# design.net
KiCad netlist of a schematic drawn in Altium Designer
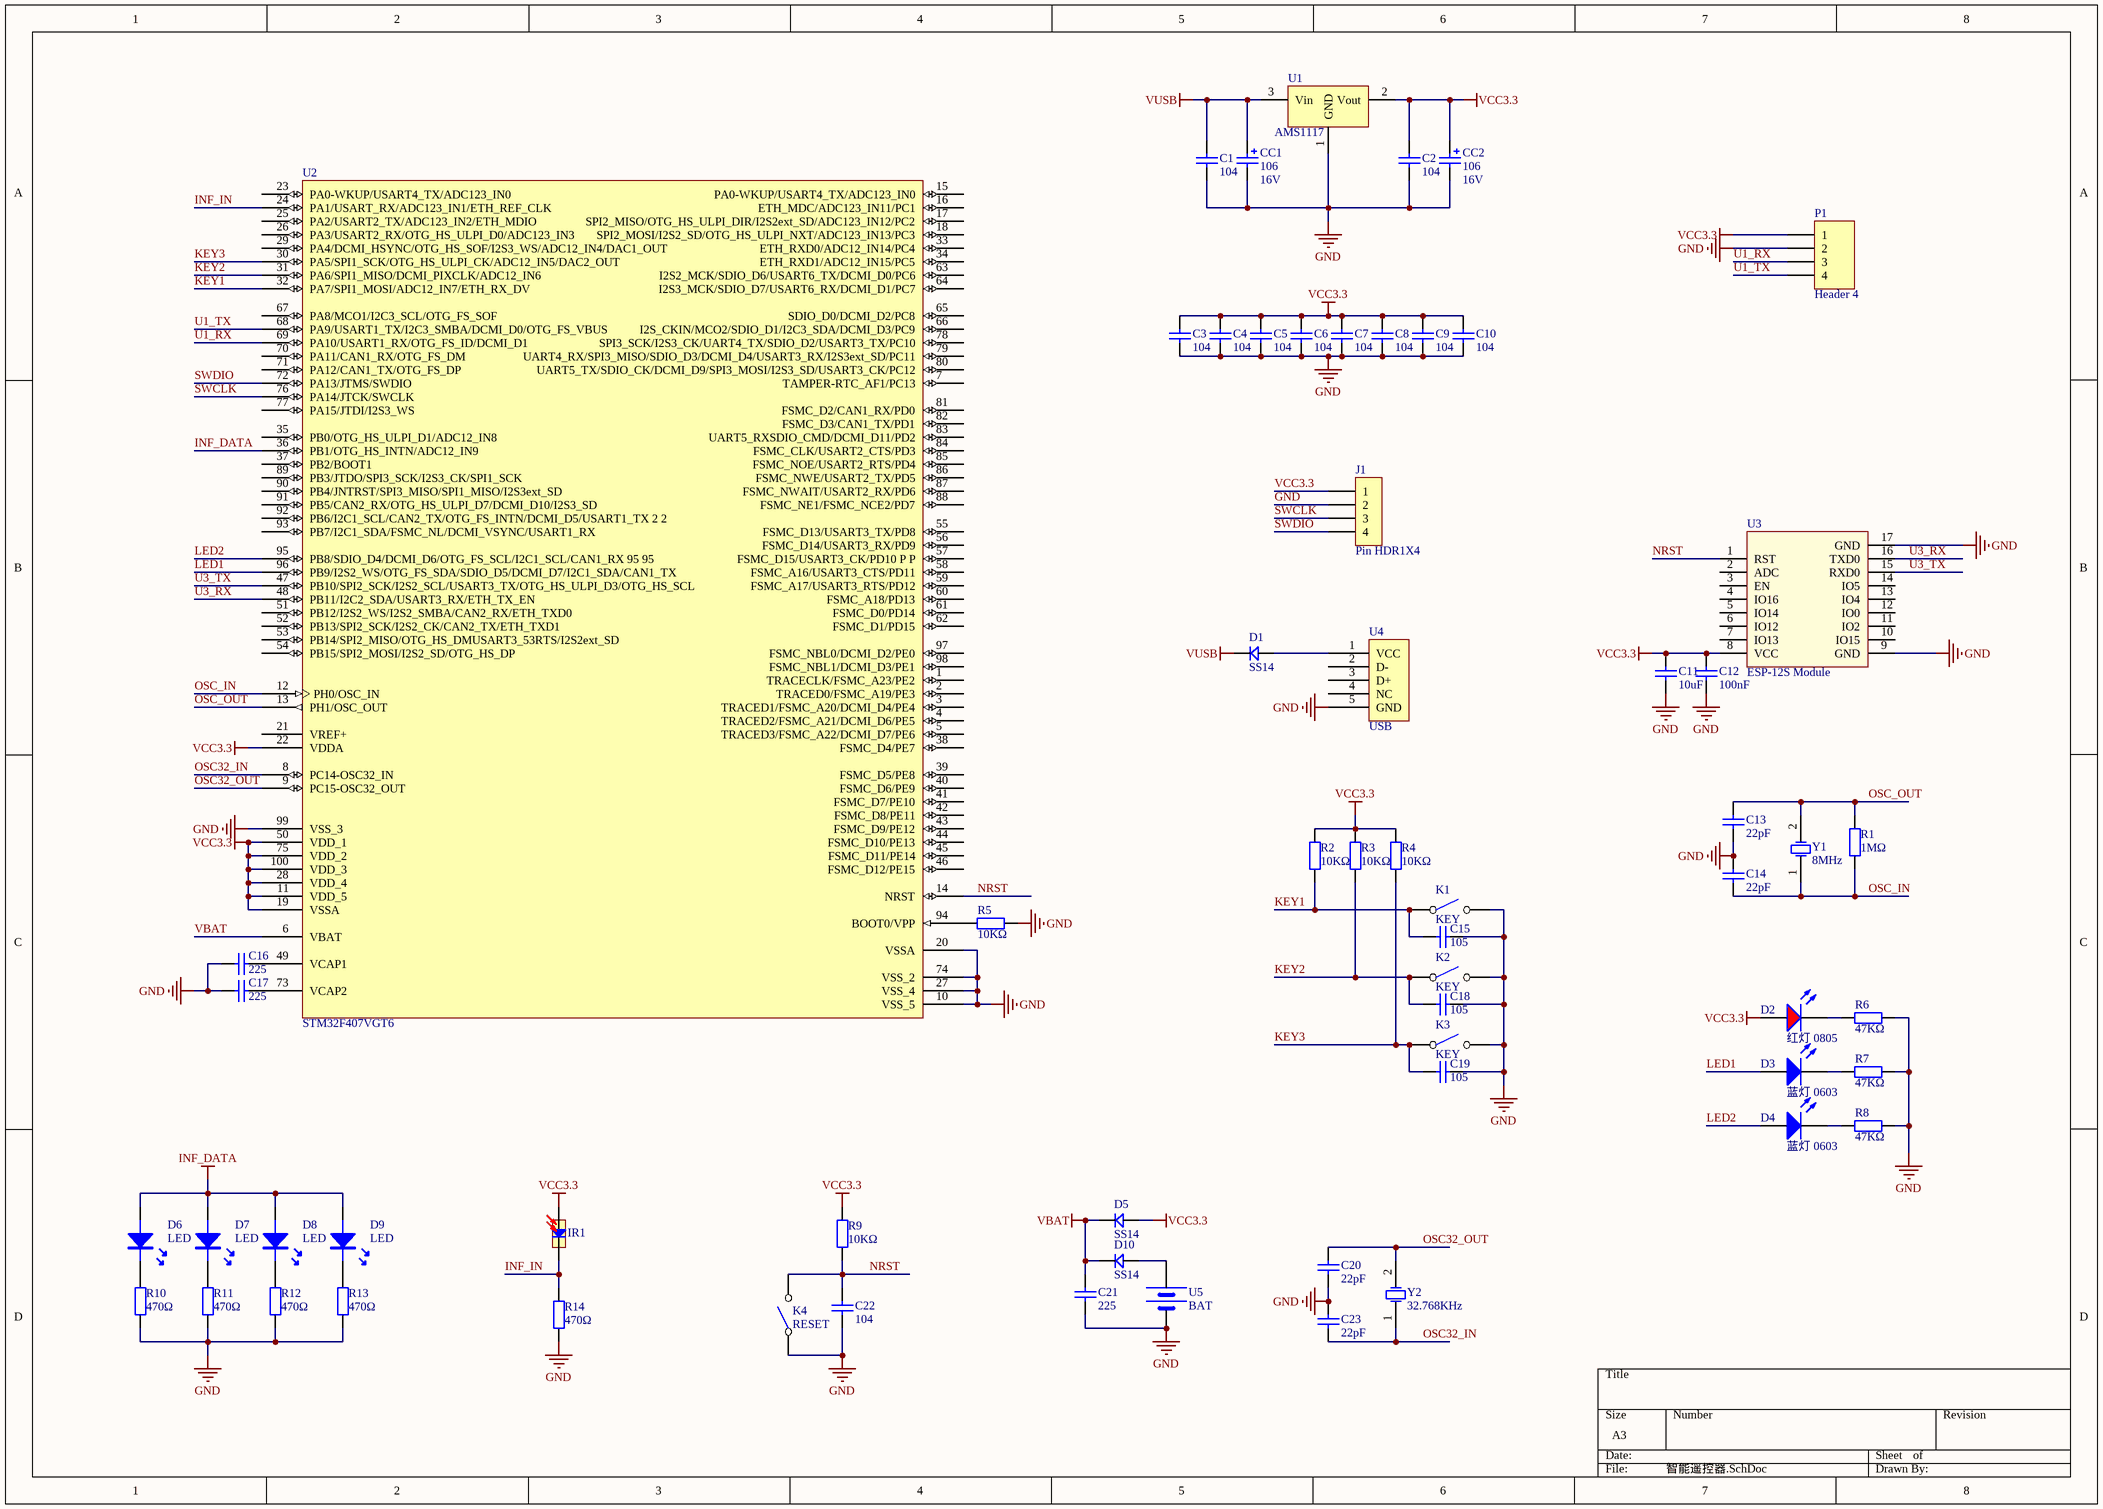
[diagram p0: 智能遥控器.SchDoc]

(export (version "E")
  (design (tool "Eeschema 10.0.6"))
  (components
    (comp (ref "C1")
      (value "104")
      (footprint "LC-0805_C")
      (description "贴片电容")
      (libsource (lib "Miscellaneous Devices LC") (part "0805 6.8nF (682) 10% 50V"))
    )
    (comp (ref "C2")
      (value "104")
      (footprint "LC-0805_C")
      (description "贴片电容")
      (libsource (lib "Miscellaneous Devices LC") (part "0805 6.8nF (682) 10% 50V"))
    )
    (comp (ref "C3")
      (value "104")
      (footprint "LC-0805_C")
      (description "贴片电容")
      (libsource (lib "Miscellaneous Devices LC") (part "0805 6.8nF (682) 10% 50V"))
    )
    (comp (ref "C4")
      (value "104")
      (footprint "LC-0805_C")
      (description "贴片电容")
      (libsource (lib "Miscellaneous Devices LC") (part "0805 6.8nF (682) 10% 50V"))
    )
    (comp (ref "C5")
      (value "104")
      (footprint "LC-0805_C")
      (description "贴片电容")
      (libsource (lib "Miscellaneous Devices LC") (part "0805 6.8nF (682) 10% 50V"))
    )
    (comp (ref "C6")
      (value "104")
      (footprint "LC-0805_C")
      (description "贴片电容")
      (libsource (lib "Miscellaneous Devices LC") (part "0805 6.8nF (682) 10% 50V"))
    )
    (comp (ref "C7")
      (value "104")
      (footprint "LC-0805_C")
      (description "贴片电容")
      (libsource (lib "Miscellaneous Devices LC") (part "0805 6.8nF (682) 10% 50V"))
    )
    (comp (ref "C8")
      (value "104")
      (footprint "LC-0805_C")
      (description "贴片电容")
      (libsource (lib "Miscellaneous Devices LC") (part "0805 6.8nF (682) 10% 50V"))
    )
    (comp (ref "C9")
      (value "104")
      (footprint "LC-0805_C")
      (description "贴片电容")
      (libsource (lib "Miscellaneous Devices LC") (part "0805 6.8nF (682) 10% 50V"))
    )
    (comp (ref "C10")
      (value "104")
      (footprint "LC-0805_C")
      (description "贴片电容")
      (libsource (lib "Miscellaneous Devices LC") (part "0805 6.8nF (682) 10% 50V"))
    )
    (comp (ref "C11")
      (value "10uF")
      (footprint "LC-0805_C")
      (description "贴片电容")
      (libsource (lib "Miscellaneous Devices LC") (part "0805 6.8nF (682) 10% 50V"))
    )
    (comp (ref "C12")
      (value "100nF")
      (footprint "LC-0805_C")
      (description "贴片电容")
      (libsource (lib "Miscellaneous Devices LC") (part "0805 6.8nF (682) 10% 50V"))
    )
    (comp (ref "C13")
      (value "22pF")
      (footprint "LC-0805_C")
      (description "贴片电容")
      (libsource (lib "Miscellaneous Devices LC") (part "0805 6pF (6R0) 0.25pF 50V"))
    )
    (comp (ref "C14")
      (value "22pF")
      (footprint "LC-0805_C")
      (description "贴片电容")
      (libsource (lib "Miscellaneous Devices LC") (part "0805 6pF (6R0) 0.25pF 50V"))
    )
    (comp (ref "C15")
      (value "105")
      (footprint "LC-0805_C")
      (description "贴片电容")
      (libsource (lib "Miscellaneous Devices LC") (part "0805 6.8nF (682) 10% 50V"))
    )
    (comp (ref "C16")
      (value "225")
      (footprint "LC-0805_C")
      (description "贴片电容")
      (libsource (lib "Miscellaneous Devices LC") (part "0805 6.8nF (682) 10% 50V"))
    )
    (comp (ref "C17")
      (value "225")
      (footprint "LC-0805_C")
      (description "贴片电容")
      (libsource (lib "Miscellaneous Devices LC") (part "0805 6.8nF (682) 10% 50V"))
    )
    (comp (ref "C18")
      (value "105")
      (footprint "LC-0805_C")
      (description "贴片电容")
      (libsource (lib "Miscellaneous Devices LC") (part "0805 6.8nF (682) 10% 50V"))
    )
    (comp (ref "C19")
      (value "105")
      (footprint "LC-0805_C")
      (description "贴片电容")
      (libsource (lib "Miscellaneous Devices LC") (part "0805 6.8nF (682) 10% 50V"))
    )
    (comp (ref "C20")
      (value "22pF")
      (footprint "LC-0805_C")
      (description "贴片电容")
      (libsource (lib "Miscellaneous Devices LC") (part "0805 6pF (6R0) 0.25pF 50V"))
    )
    (comp (ref "C21")
      (value "225")
      (footprint "LC-0805_C")
      (description "贴片电容")
      (libsource (lib "Miscellaneous Devices LC") (part "0805 6.8nF (682) 10% 50V"))
    )
    (comp (ref "C22")
      (value "104")
      (footprint "LC-0805_C")
      (description "贴片电容")
      (libsource (lib "Miscellaneous Devices LC") (part "0805 330nF (334) 10% 50V"))
    )
    (comp (ref "C23")
      (value "22pF")
      (footprint "LC-0805_C")
      (description "贴片电容")
      (libsource (lib "Miscellaneous Devices LC") (part "0805 6pF (6R0) 0.25pF 50V"))
    )
    (comp (ref "CC1")
      (value "Cap Tan C")
      (footprint "TAN-C-6032")
      (description "Polarized Capacitor (Radial)")
      (fields
        (field (name "CAPACITANCE") "106")
        (field (name "VOLTAGE") "16V")
        (field (name "PUBLISHER") "Altium Limited")
      )
      (libsource (lib "MyLib") (part "Cap Tan C"))
    )
    (comp (ref "CC2")
      (value "Cap Tan C")
      (footprint "TAN-C-6032")
      (description "Polarized Capacitor (Radial)")
      (fields
        (field (name "CAPACITANCE") "106")
        (field (name "VOLTAGE") "16V")
        (field (name "PUBLISHER") "Altium Limited")
      )
      (libsource (lib "MyLib") (part "Cap Tan C"))
    )
    (comp (ref "D1")
      (value "SS14")
      (footprint "Miscellaneous Devices LC:LC-SOD-123")
      (libsource (lib "Explorer STM32F407封装库") (part "D"))
    )
    (comp (ref "D2")
      (value "红灯 0805")
      (footprint "LC-0805_LED_S1")
      (description "发光二极管")
      (libsource (lib "Miscellaneous Devices LC") (part "0805 红灯"))
    )
    (comp (ref "D3")
      (value "蓝灯 0603")
      (footprint "Miscellaneous Devices LC:LC-0805_LED_S1")
      (description "发光二极管")
      (libsource (lib "Miscellaneous Devices LC") (part "0603 蓝灯"))
    )
    (comp (ref "D4")
      (value "蓝灯 0603")
      (footprint "Miscellaneous Devices LC:LC-0805_LED_S1")
      (description "发光二极管")
      (libsource (lib "Miscellaneous Devices LC") (part "0603 蓝灯"))
    )
    (comp (ref "D5")
      (value "SS14")
      (footprint "Miscellaneous Devices LC:LC-SOD-123")
      (libsource (lib "Explorer STM32F407封装库") (part "D"))
    )
    (comp (ref "D6") (value "LED") (footprint "LED5-RED") (libsource (lib "LED") (part "LED")))
    (comp (ref "D7") (value "LED") (footprint "LED5-RED") (libsource (lib "LED") (part "LED")))
    (comp (ref "D8") (value "LED") (footprint "LED5-RED") (libsource (lib "LED") (part "LED")))
    (comp (ref "D9") (value "LED") (footprint "LED5-RED") (libsource (lib "LED") (part "LED")))
    (comp (ref "D10")
      (value "SS14")
      (footprint "Miscellaneous Devices LC:LC-SOD-123")
      (libsource (lib "Explorer STM32F407封装库") (part "D"))
    )
    (comp (ref "IR1")
      (value "IR")
      (footprint "MyLib:LED-R5-H9-SINGLE-B")
      (description "RED Remote Receiver")
      (libsource (lib "MyLib") (part "IR"))
    )
    (comp (ref "J1")
      (value "Pin HDR1X4")
      (footprint "Pin HDR1X4/2.54mm-S")
      (libsource (lib "排针") (part "Pin HDR1X4"))
    )
    (comp (ref "K1")
      (value "KEY")
      (footprint "MyLib:KEY_2")
      (description "微动开关")
      (libsource (lib "MyLib") (part "KEY"))
    )
    (comp (ref "K2")
      (value "KEY")
      (footprint "MyLib:KEY_2")
      (description "微动开关")
      (libsource (lib "MyLib") (part "KEY"))
    )
    (comp (ref "K3")
      (value "KEY")
      (footprint "MyLib:KEY_2")
      (description "微动开关")
      (libsource (lib "MyLib") (part "KEY"))
    )
    (comp (ref "K4")
      (value "RESET")
      (footprint "MyLib:KEY_2")
      (description "微动开关")
      (libsource (lib "MyLib") (part "KEY"))
    )
    (comp (ref "P1")
      (value "Header 4")
      (footprint "MyLib:HDR1X4")
      (description "Header, 4-Pin")
      (fields (field (name "PUBLISHER") "Altium Limited"))
      (libsource (lib "MyLib") (part "Header 4"))
    )
    (comp (ref "R1")
      (value "1MΩ")
      (footprint "LC-0805_R")
      (description "贴片电阻")
      (libsource (lib "Miscellaneous Devices LC") (part "0805 390KΩ (3903) 1%"))
    )
    (comp (ref "R2")
      (value "10KΩ")
      (footprint "LC-0805_R")
      (description "贴片电阻")
      (libsource (lib "Miscellaneous Devices LC") (part "0805 11KΩ (1102) 1%"))
    )
    (comp (ref "R3")
      (value "10KΩ")
      (footprint "LC-0805_R")
      (description "贴片电阻")
      (libsource (lib "Miscellaneous Devices LC") (part "0805 11KΩ (1102) 1%"))
    )
    (comp (ref "R4")
      (value "10KΩ")
      (footprint "LC-0805_R")
      (description "贴片电阻")
      (libsource (lib "Miscellaneous Devices LC") (part "0805 11KΩ (1102) 1%"))
    )
    (comp (ref "R5")
      (value "10KΩ")
      (footprint "LC-0805_R")
      (description "贴片电阻")
      (libsource (lib "Miscellaneous Devices LC") (part "0805 1.8KΩ (1801) 1%"))
    )
    (comp (ref "R6")
      (value "47KΩ")
      (footprint "LC-0805_R")
      (description "贴片电阻")
      (libsource (lib "") (part "0805 11KΩ (1102) 1%_1"))
    )
    (comp (ref "R7")
      (value "47KΩ")
      (footprint "LC-0805_R")
      (description "贴片电阻")
      (libsource (lib "") (part "0805 11KΩ (1102) 1%_1"))
    )
    (comp (ref "R8")
      (value "47KΩ")
      (footprint "LC-0805_R")
      (description "贴片电阻")
      (libsource (lib "") (part "0805 11KΩ (1102) 1%_1"))
    )
    (comp (ref "R9")
      (value "10KΩ")
      (footprint "LC-0805_R")
      (description "贴片电阻")
      (libsource (lib "Miscellaneous Devices LC") (part "0805 390KΩ (3903) 1%"))
    )
    (comp (ref "R10")
      (value "470Ω")
      (footprint "LC-0805_R")
      (description "贴片电阻")
      (libsource (lib "Miscellaneous Devices LC") (part "0805 11KΩ (1102) 1%"))
    )
    (comp (ref "R11")
      (value "470Ω")
      (footprint "LC-0805_R")
      (description "贴片电阻")
      (libsource (lib "Miscellaneous Devices LC") (part "0805 11KΩ (1102) 1%"))
    )
    (comp (ref "R12")
      (value "470Ω")
      (footprint "LC-0805_R")
      (description "贴片电阻")
      (libsource (lib "Miscellaneous Devices LC") (part "0805 11KΩ (1102) 1%"))
    )
    (comp (ref "R13")
      (value "470Ω")
      (footprint "LC-0805_R")
      (description "贴片电阻")
      (libsource (lib "Miscellaneous Devices LC") (part "0805 11KΩ (1102) 1%"))
    )
    (comp (ref "R14")
      (value "470Ω")
      (footprint "LC-0805_R")
      (description "贴片电阻")
      (libsource (lib "Miscellaneous Devices LC") (part "0805 11KΩ (1102) 1%"))
    )
    (comp (ref "U1")
      (value "AMS1117")
      (footprint "MyLib:SOT-223")
      (description "3.3V电压转换器AMS1117")
      (libsource (lib "My Footprint") (part "AMS1117"))
    )
    (comp (ref "U2")
      (value "STM32F407VGT6")
      (footprint "STM32系列:LQFP100 14x14")
      (libsource (lib "STM32F407系列") (part "STM32F407VGT6"))
    )
    (comp (ref "U3")
      (value "ESP-12S Module")
      (footprint "ESP-12S Module")
      (libsource (lib "MyLib") (part "ESP-12S Module"))
    )
    (comp (ref "U4") (value "USB") (footprint "MyLib:USB_B") (libsource (lib "MyLib") (part "USB")))
    (comp (ref "U5")
      (value "BAT")
      (footprint "MyLib:CR1220_A")
      (description "纽扣电池座CR1220")
      (libsource (lib "MyLib") (part "BAT"))
    )
    (comp (ref "Y1")
      (value "8MHz")
      (footprint "MyLib:XTAL-SMD")
      (description "晶体振荡器")
      (fields (field (name "PUBLISHER") "Altium Limited"))
      (libsource (lib "MyLib") (part "XTAL"))
    )
    (comp (ref "Y2")
      (value "32.768KHz")
      (footprint "晶振:OSC-3x8-WI-B")
      (description "晶体振荡器")
      (fields (field (name "PUBLISHER") "Altium Limited"))
      (libsource (lib "MyLib") (part "XTAL"))
    )
  )
  (nets
    (net (code "1") (name "/INF_IN") (class "Default")
      (node (ref "IR1") (pin "2") (pinfunction "GND_2") (pintype "passive"))
      (node (ref "R14") (pin "2") (pinfunction "2_2") (pintype "passive"))
      (node (ref "U2") (pin "24") (pinfunction "PA1/USART_RX/ADC123_IN1/ETH_REF_CLK_24") (pintype "bidirectional"))
    )
    (net (code "2") (name "/KEY1") (class "Default")
      (node (ref "C15") (pin "1") (pinfunction "1_1") (pintype "passive"))
      (node (ref "K1") (pin "1") (pinfunction "1_1") (pintype "passive"))
      (node (ref "R2") (pin "1") (pinfunction "1_1") (pintype "passive"))
      (node (ref "U2") (pin "32") (pinfunction "PA7/SPI1_MOSI/ADC12_IN7/ETH_RX_DV_32") (pintype "bidirectional"))
    )
    (net (code "3") (name "/KEY2") (class "Default")
      (node (ref "C18") (pin "1") (pinfunction "1_1") (pintype "passive"))
      (node (ref "K2") (pin "1") (pinfunction "1_1") (pintype "passive"))
      (node (ref "R3") (pin "1") (pinfunction "1_1") (pintype "passive"))
      (node (ref "U2") (pin "31") (pinfunction "PA6/SPI1_MISO/DCMI_PIXCLK/ADC12_IN6_31") (pintype "bidirectional"))
    )
    (net (code "4") (name "/KEY3") (class "Default")
      (node (ref "C19") (pin "1") (pinfunction "1_1") (pintype "passive"))
      (node (ref "K3") (pin "1") (pinfunction "1_1") (pintype "passive"))
      (node (ref "R4") (pin "1") (pinfunction "1_1") (pintype "passive"))
      (node (ref "U2") (pin "30") (pinfunction "PA5/SPI1_SCK/OTG_HS_ULPI_CK/ADC12_IN5/DAC2_OUT_30") (pintype "bidirectional"))
    )
    (net (code "5") (name "/LED1") (class "Default")
      (node (ref "D3") (pin "A") (pinfunction "A_A") (pintype "passive"))
      (node (ref "U2") (pin "96") (pinfunction "PB9/I2S2_WS/OTG_FS_SDA/SDIO_D5/DCMI_D7/I2C1_SDA/CAN1_TX_96") (pintype "bidirectional"))
    )
    (net (code "6") (name "/LED2") (class "Default")
      (node (ref "D4") (pin "A") (pinfunction "A_A") (pintype "passive"))
      (node (ref "U2") (pin "95") (pinfunction "PB8/SDIO_D4/DCMI_D6/OTG_FS_SCL/I2C1_SCL/CAN1_RX_95_95_95") (pintype "bidirectional"))
    )
    (net (code "7") (name "/NRST") (class "Default")
      (node (ref "C22") (pin "2") (pinfunction "2_2") (pintype "passive"))
      (node (ref "K4") (pin "2") (pinfunction "2_2") (pintype "passive"))
      (node (ref "R9") (pin "1") (pinfunction "1_1") (pintype "passive"))
      (node (ref "U2") (pin "14") (pinfunction "NRST_14") (pintype "bidirectional"))
      (node (ref "U3") (pin "1") (pinfunction "RST_1") (pintype "passive"))
    )
    (net (code "8") (name "/OSC32_IN") (class "Default")
      (node (ref "C23") (pin "1") (pinfunction "1_1") (pintype "passive"))
      (node (ref "U2") (pin "8") (pinfunction "PC14-OSC32_IN_8") (pintype "bidirectional"))
      (node (ref "Y2") (pin "1") (pinfunction "OSC1_1") (pintype "passive"))
    )
    (net (code "9") (name "/OSC32_OUT") (class "Default")
      (node (ref "C20") (pin "2") (pinfunction "2_2") (pintype "passive"))
      (node (ref "U2") (pin "9") (pinfunction "PC15-OSC32_OUT_9") (pintype "bidirectional"))
      (node (ref "Y2") (pin "2") (pinfunction "OSC2_2") (pintype "passive"))
    )
    (net (code "10") (name "/OSC_IN") (class "Default")
      (node (ref "C14") (pin "1") (pinfunction "1_1") (pintype "passive"))
      (node (ref "R1") (pin "1") (pinfunction "1_1") (pintype "passive"))
      (node (ref "U2") (pin "12") (pinfunction "PH0/OSC_IN_12") (pintype "input"))
      (node (ref "Y1") (pin "1") (pinfunction "OSC1_1") (pintype "passive"))
    )
    (net (code "11") (name "/OSC_OUT") (class "Default")
      (node (ref "C13") (pin "2") (pinfunction "2_2") (pintype "passive"))
      (node (ref "R1") (pin "2") (pinfunction "2_2") (pintype "passive"))
      (node (ref "U2") (pin "13") (pinfunction "PH1/OSC_OUT_13") (pintype "output"))
      (node (ref "Y1") (pin "2") (pinfunction "OSC2_2") (pintype "passive"))
    )
    (net (code "12") (name "/SWCLK") (class "Default")
      (node (ref "J1") (pin "3") (pinfunction "3_3") (pintype "passive"))
      (node (ref "U2") (pin "76") (pinfunction "PA14/JTCK/SWCLK_76") (pintype "bidirectional"))
    )
    (net (code "13") (name "/SWDIO") (class "Default")
      (node (ref "J1") (pin "4") (pinfunction "4_4") (pintype "passive"))
      (node (ref "U2") (pin "72") (pinfunction "PA13/JTMS/SWDIO_72") (pintype "bidirectional"))
    )
    (net (code "14") (name "/U1_RX") (class "Default")
      (node (ref "P1") (pin "3") (pinfunction "3_3") (pintype "passive"))
      (node (ref "U2") (pin "69") (pinfunction "PA10/USART1_RX/OTG_FS_ID/DCMI_D1_69") (pintype "bidirectional"))
    )
    (net (code "15") (name "/U1_TX") (class "Default")
      (node (ref "P1") (pin "4") (pinfunction "4_4") (pintype "passive"))
      (node (ref "U2") (pin "68") (pinfunction "PA9/USART1_TX/I2C3_SMBA/DCMI_D0/OTG_FS_VBUS_68") (pintype "bidirectional"))
    )
    (net (code "16") (name "/U3_RX") (class "Default")
      (node (ref "U2") (pin "48") (pinfunction "PB11/I2C2_SDA/USART3_RX/ETH_TX_EN_48") (pintype "bidirectional"))
      (node (ref "U3") (pin "16") (pinfunction "TXD0_16") (pintype "passive"))
    )
    (net (code "17") (name "/U3_TX") (class "Default")
      (node (ref "U2") (pin "47") (pinfunction "PB10/SPI2_SCK/I2S2_SCL/USART3_TX/OTG_HS_ULPI_D3/OTG_HS_SCL_47") (pintype "bidirectional"))
      (node (ref "U3") (pin "15") (pinfunction "RXD0_15") (pintype "passive"))
    )
    (net (code "18") (name "GND") (class "Default")
      (node (ref "C1") (pin "1") (pinfunction "1_1") (pintype "passive"))
      (node (ref "C10") (pin "1") (pinfunction "1_1") (pintype "passive"))
      (node (ref "C11") (pin "1") (pinfunction "1_1") (pintype "passive"))
      (node (ref "C12") (pin "1") (pinfunction "1_1") (pintype "passive"))
      (node (ref "C13") (pin "1") (pinfunction "1_1") (pintype "passive"))
      (node (ref "C14") (pin "2") (pinfunction "2_2") (pintype "passive"))
      (node (ref "C15") (pin "2") (pinfunction "2_2") (pintype "passive"))
      (node (ref "C16") (pin "1") (pinfunction "1_1") (pintype "passive"))
      (node (ref "C17") (pin "1") (pinfunction "1_1") (pintype "passive"))
      (node (ref "C18") (pin "2") (pinfunction "2_2") (pintype "passive"))
      (node (ref "C19") (pin "2") (pinfunction "2_2") (pintype "passive"))
      (node (ref "C2") (pin "1") (pinfunction "1_1") (pintype "passive"))
      (node (ref "C20") (pin "1") (pinfunction "1_1") (pintype "passive"))
      (node (ref "C21") (pin "1") (pinfunction "1_1") (pintype "passive"))
      (node (ref "C22") (pin "1") (pinfunction "1_1") (pintype "passive"))
      (node (ref "C23") (pin "2") (pinfunction "2_2") (pintype "passive"))
      (node (ref "C3") (pin "1") (pinfunction "1_1") (pintype "passive"))
      (node (ref "C4") (pin "1") (pinfunction "1_1") (pintype "passive"))
      (node (ref "C5") (pin "1") (pinfunction "1_1") (pintype "passive"))
      (node (ref "C6") (pin "1") (pinfunction "1_1") (pintype "passive"))
      (node (ref "C7") (pin "1") (pinfunction "1_1") (pintype "passive"))
      (node (ref "C8") (pin "1") (pinfunction "1_1") (pintype "passive"))
      (node (ref "C9") (pin "1") (pinfunction "1_1") (pintype "passive"))
      (node (ref "CC1") (pin "1") (pinfunction "2_1") (pintype "passive"))
      (node (ref "CC2") (pin "1") (pinfunction "2_1") (pintype "passive"))
      (node (ref "J1") (pin "2") (pinfunction "2_2") (pintype "passive"))
      (node (ref "K1") (pin "2") (pinfunction "2_2") (pintype "passive"))
      (node (ref "K2") (pin "2") (pinfunction "2_2") (pintype "passive"))
      (node (ref "K3") (pin "2") (pinfunction "2_2") (pintype "passive"))
      (node (ref "K4") (pin "1") (pinfunction "1_1") (pintype "passive"))
      (node (ref "P1") (pin "2") (pinfunction "2_2") (pintype "passive"))
      (node (ref "R10") (pin "1") (pinfunction "1_1") (pintype "passive"))
      (node (ref "R11") (pin "1") (pinfunction "1_1") (pintype "passive"))
      (node (ref "R12") (pin "1") (pinfunction "1_1") (pintype "passive"))
      (node (ref "R13") (pin "1") (pinfunction "1_1") (pintype "passive"))
      (node (ref "R14") (pin "1") (pinfunction "1_1") (pintype "passive"))
      (node (ref "R5") (pin "2") (pinfunction "2_2") (pintype "passive"))
      (node (ref "R6") (pin "2") (pinfunction "2_2") (pintype "passive"))
      (node (ref "R7") (pin "2") (pinfunction "2_2") (pintype "passive"))
      (node (ref "R8") (pin "2") (pinfunction "2_2") (pintype "passive"))
      (node (ref "U1") (pin "1") (pinfunction "GND_1") (pintype "passive"))
      (node (ref "U2") (pin "10") (pinfunction "VSS_5_10") (pintype "power_in"))
      (node (ref "U2") (pin "20") (pinfunction "VSSA_20") (pintype "power_in"))
      (node (ref "U2") (pin "27") (pinfunction "VSS_4_27") (pintype "power_in"))
      (node (ref "U2") (pin "74") (pinfunction "VSS_2_74") (pintype "power_in"))
      (node (ref "U2") (pin "99") (pinfunction "VSS_3_99") (pintype "power_in"))
      (node (ref "U3") (pin "17") (pinfunction "GND_17") (pintype "passive"))
      (node (ref "U3") (pin "9") (pinfunction "GND_9") (pintype "passive"))
      (node (ref "U4") (pin "5") (pinfunction "GND_5") (pintype "passive"))
      (node (ref "U5") (pin "2") (pinfunction "GND_2") (pintype "passive"))
    )
    (net (code "19") (name "INF_DATA") (class "Default")
      (node (ref "D6") (pin "A") (pinfunction "A_A") (pintype "passive"))
      (node (ref "D7") (pin "A") (pinfunction "A_A") (pintype "passive"))
      (node (ref "D8") (pin "A") (pinfunction "A_A") (pintype "passive"))
      (node (ref "D9") (pin "A") (pinfunction "A_A") (pintype "passive"))
      (node (ref "U2") (pin "36") (pinfunction "PB1/OTG_HS_INTN/ADC12_IN9_36") (pintype "bidirectional"))
    )
    (net (code "20") (name "Net-(D2-PadK)") (class "Default")
      (node (ref "D2") (pin "K") (pinfunction "K_K") (pintype "passive"))
      (node (ref "R6") (pin "1") (pinfunction "1_1") (pintype "passive"))
    )
    (net (code "21") (name "Net-(D3-PadK)") (class "Default")
      (node (ref "D3") (pin "K") (pinfunction "K_K") (pintype "passive"))
      (node (ref "R7") (pin "1") (pinfunction "1_1") (pintype "passive"))
    )
    (net (code "22") (name "Net-(D4-PadK)") (class "Default")
      (node (ref "D4") (pin "K") (pinfunction "K_K") (pintype "passive"))
      (node (ref "R8") (pin "1") (pinfunction "1_1") (pintype "passive"))
    )
    (net (code "23") (name "Net-(D6-PadK)") (class "Default")
      (node (ref "D6") (pin "K") (pinfunction "K_K") (pintype "passive"))
      (node (ref "R10") (pin "2") (pinfunction "2_2") (pintype "passive"))
    )
    (net (code "24") (name "Net-(D7-PadK)") (class "Default")
      (node (ref "D7") (pin "K") (pinfunction "K_K") (pintype "passive"))
      (node (ref "R11") (pin "2") (pinfunction "2_2") (pintype "passive"))
    )
    (net (code "25") (name "Net-(D8-PadK)") (class "Default")
      (node (ref "D8") (pin "K") (pinfunction "K_K") (pintype "passive"))
      (node (ref "R12") (pin "2") (pinfunction "2_2") (pintype "passive"))
    )
    (net (code "26") (name "Net-(D9-PadK)") (class "Default")
      (node (ref "D9") (pin "K") (pinfunction "K_K") (pintype "passive"))
      (node (ref "R13") (pin "2") (pinfunction "2_2") (pintype "passive"))
    )
    (net (code "27") (name "Net-(U2-BOOT0{slash}VPP)") (class "Default")
      (node (ref "R5") (pin "1") (pinfunction "1_1") (pintype "passive"))
      (node (ref "U2") (pin "94") (pinfunction "BOOT0/VPP_94") (pintype "input"))
    )
    (net (code "28") (name "Net-(U2-VCAP1)") (class "Default")
      (node (ref "C16") (pin "2") (pinfunction "2_2") (pintype "passive"))
      (node (ref "U2") (pin "49") (pinfunction "VCAP1_49") (pintype "power_in"))
    )
    (net (code "29") (name "Net-(U2-VCAP2)") (class "Default")
      (node (ref "C17") (pin "2") (pinfunction "2_2") (pintype "passive"))
      (node (ref "U2") (pin "73") (pinfunction "VCAP2_73") (pintype "passive"))
    )
    (net (code "30") (name "Net-(U4-VCC)") (class "Default")
      (node (ref "D1") (pin "1") (pintype "passive"))
      (node (ref "U4") (pin "1") (pinfunction "VCC_1") (pintype "passive"))
    )
    (net (code "31") (name "Net-(U5-VCC)") (class "Default")
      (node (ref "D10") (pin "1") (pintype "passive"))
      (node (ref "U5") (pin "1") (pinfunction "VCC_1") (pintype "passive"))
    )
    (net (code "32") (name "VBAT") (class "Default")
      (node (ref "C21") (pin "2") (pinfunction "2_2") (pintype "passive"))
      (node (ref "D10") (pin "2") (pintype "passive"))
      (node (ref "D5") (pin "2") (pintype "passive"))
      (node (ref "U2") (pin "6") (pinfunction "VBAT_6") (pintype "power_in"))
    )
    (net (code "33") (name "VCC3.3") (class "Default")
      (node (ref "C10") (pin "2") (pinfunction "2_2") (pintype "passive"))
      (node (ref "C11") (pin "2") (pinfunction "2_2") (pintype "passive"))
      (node (ref "C12") (pin "2") (pinfunction "2_2") (pintype "passive"))
      (node (ref "C2") (pin "2") (pinfunction "2_2") (pintype "passive"))
      (node (ref "C3") (pin "2") (pinfunction "2_2") (pintype "passive"))
      (node (ref "C4") (pin "2") (pinfunction "2_2") (pintype "passive"))
      (node (ref "C5") (pin "2") (pinfunction "2_2") (pintype "passive"))
      (node (ref "C6") (pin "2") (pinfunction "2_2") (pintype "passive"))
      (node (ref "C7") (pin "2") (pinfunction "2_2") (pintype "passive"))
      (node (ref "C8") (pin "2") (pinfunction "2_2") (pintype "passive"))
      (node (ref "C9") (pin "2") (pinfunction "2_2") (pintype "passive"))
      (node (ref "CC2") (pin "2") (pinfunction "1_2") (pintype "passive"))
      (node (ref "D2") (pin "A") (pinfunction "A_A") (pintype "passive"))
      (node (ref "D5") (pin "1") (pintype "passive"))
      (node (ref "IR1") (pin "1") (pinfunction "VCC_1") (pintype "passive"))
      (node (ref "J1") (pin "1") (pinfunction "1_1") (pintype "passive"))
      (node (ref "P1") (pin "1") (pinfunction "1_1") (pintype "passive"))
      (node (ref "R2") (pin "2") (pinfunction "2_2") (pintype "passive"))
      (node (ref "R3") (pin "2") (pinfunction "2_2") (pintype "passive"))
      (node (ref "R4") (pin "2") (pinfunction "2_2") (pintype "passive"))
      (node (ref "R9") (pin "2") (pinfunction "2_2") (pintype "passive"))
      (node (ref "U1") (pin "2") (pinfunction "Vout_2") (pintype "passive"))
      (node (ref "U2") (pin "100") (pinfunction "VDD_3_100") (pintype "power_in"))
      (node (ref "U2") (pin "11") (pinfunction "VDD_5_11") (pintype "power_in"))
      (node (ref "U2") (pin "19") (pinfunction "VSSA_19") (pintype "power_in"))
      (node (ref "U2") (pin "22") (pinfunction "VDDA_22") (pintype "power_in"))
      (node (ref "U2") (pin "28") (pinfunction "VDD_4_28") (pintype "power_in"))
      (node (ref "U2") (pin "50") (pinfunction "VDD_1_50") (pintype "power_in"))
      (node (ref "U2") (pin "75") (pinfunction "VDD_2_75") (pintype "power_in"))
      (node (ref "U3") (pin "8") (pinfunction "VCC_8") (pintype "passive"))
    )
    (net (code "34") (name "VUSB") (class "Default")
      (node (ref "C1") (pin "2") (pinfunction "2_2") (pintype "passive"))
      (node (ref "CC1") (pin "2") (pinfunction "1_2") (pintype "passive"))
      (node (ref "D1") (pin "2") (pintype "passive"))
      (node (ref "U1") (pin "3") (pinfunction "Vin_3") (pintype "passive"))
    )
    (net (code "35") (name "unconnected-(U2-ETH_MDC{slash}ADC123_IN11{slash}PC1-Pad16)") (class "Default")
      (node (ref "U2") (pin "16") (pinfunction "ETH_MDC/ADC123_IN11/PC1_16") (pintype "bidirectional"))
    )
    (net (code "36") (name "unconnected-(U2-ETH_RXD0{slash}ADC12_IN14{slash}PC4-Pad33)") (class "Default")
      (node (ref "U2") (pin "33") (pinfunction "ETH_RXD0/ADC12_IN14/PC4_33") (pintype "bidirectional"))
    )
    (net (code "37") (name "unconnected-(U2-ETH_RXD1{slash}ADC12_IN15{slash}PC5-Pad34)") (class "Default")
      (node (ref "U2") (pin "34") (pinfunction "ETH_RXD1/ADC12_IN15/PC5_34") (pintype "bidirectional"))
    )
    (net (code "38") (name "unconnected-(U2-FSMC_A16{slash}USART3_CTS{slash}PD11-Pad58)") (class "Default")
      (node (ref "U2") (pin "58") (pinfunction "FSMC_A16/USART3_CTS/PD11_58") (pintype "bidirectional"))
    )
    (net (code "39") (name "unconnected-(U2-FSMC_A17{slash}USART3_RTS{slash}PD12-Pad59)") (class "Default")
      (node (ref "U2") (pin "59") (pinfunction "FSMC_A17/USART3_RTS/PD12_59") (pintype "bidirectional"))
    )
    (net (code "40") (name "unconnected-(U2-FSMC_A18{slash}PD13-Pad60)") (class "Default")
      (node (ref "U2") (pin "60") (pinfunction "FSMC_A18/PD13_60") (pintype "bidirectional"))
    )
    (net (code "41") (name "unconnected-(U2-FSMC_CLK{slash}USART2_CTS{slash}PD3-Pad84)") (class "Default")
      (node (ref "U2") (pin "84") (pinfunction "FSMC_CLK/USART2_CTS/PD3_84") (pintype "bidirectional"))
    )
    (net (code "42") (name "unconnected-(U2-FSMC_D0{slash}PD14-Pad61)") (class "Default")
      (node (ref "U2") (pin "61") (pinfunction "FSMC_D0/PD14_61") (pintype "bidirectional"))
    )
    (net (code "43") (name "unconnected-(U2-FSMC_D1{slash}PD15-Pad62)") (class "Default")
      (node (ref "U2") (pin "62") (pinfunction "FSMC_D1/PD15_62") (pintype "bidirectional"))
    )
    (net (code "44") (name "unconnected-(U2-FSMC_D2{slash}CAN1_RX{slash}PD0-Pad81)") (class "Default")
      (node (ref "U2") (pin "81") (pinfunction "FSMC_D2/CAN1_RX/PD0_81") (pintype "bidirectional"))
    )
    (net (code "45") (name "unconnected-(U2-FSMC_D3{slash}CAN1_TX{slash}PD1-Pad82)") (class "Default")
      (node (ref "U2") (pin "82") (pinfunction "FSMC_D3/CAN1_TX/PD1_82") (pintype "bidirectional"))
    )
    (net (code "46") (name "unconnected-(U2-FSMC_D4{slash}PE7-Pad38)") (class "Default")
      (node (ref "U2") (pin "38") (pinfunction "FSMC_D4/PE7_38") (pintype "bidirectional"))
    )
    (net (code "47") (name "unconnected-(U2-FSMC_D5{slash}PE8-Pad39)") (class "Default")
      (node (ref "U2") (pin "39") (pinfunction "FSMC_D5/PE8_39") (pintype "bidirectional"))
    )
    (net (code "48") (name "unconnected-(U2-FSMC_D6{slash}PE9-Pad40)") (class "Default")
      (node (ref "U2") (pin "40") (pinfunction "FSMC_D6/PE9_40") (pintype "bidirectional"))
    )
    (net (code "49") (name "unconnected-(U2-FSMC_D7{slash}PE10-Pad41)") (class "Default")
      (node (ref "U2") (pin "41") (pinfunction "FSMC_D7/PE10_41") (pintype "bidirectional"))
    )
    (net (code "50") (name "unconnected-(U2-FSMC_D8{slash}PE11-Pad42)") (class "Default")
      (node (ref "U2") (pin "42") (pinfunction "FSMC_D8/PE11_42") (pintype "bidirectional"))
    )
    (net (code "51") (name "unconnected-(U2-FSMC_D9{slash}PE12-Pad43)") (class "Default")
      (node (ref "U2") (pin "43") (pinfunction "FSMC_D9/PE12_43") (pintype "bidirectional"))
    )
    (net (code "52") (name "unconnected-(U2-FSMC_D10{slash}PE13-Pad44)") (class "Default")
      (node (ref "U2") (pin "44") (pinfunction "FSMC_D10/PE13_44") (pintype "bidirectional"))
    )
    (net (code "53") (name "unconnected-(U2-FSMC_D11{slash}PE14-Pad45)") (class "Default")
      (node (ref "U2") (pin "45") (pinfunction "FSMC_D11/PE14_45") (pintype "bidirectional"))
    )
    (net (code "54") (name "unconnected-(U2-FSMC_D12{slash}PE15-Pad46)") (class "Default")
      (node (ref "U2") (pin "46") (pinfunction "FSMC_D12/PE15_46") (pintype "bidirectional"))
    )
    (net (code "55") (name "unconnected-(U2-FSMC_D13{slash}USART3_TX{slash}PD8-Pad55)") (class "Default")
      (node (ref "U2") (pin "55") (pinfunction "FSMC_D13/USART3_TX/PD8_55") (pintype "bidirectional"))
    )
    (net (code "56") (name "unconnected-(U2-FSMC_D14{slash}USART3_RX{slash}PD9-Pad56)") (class "Default")
      (node (ref "U2") (pin "56") (pinfunction "FSMC_D14/USART3_RX/PD9_56") (pintype "bidirectional"))
    )
    (net (code "57") (name "unconnected-(U2-FSMC_D15{slash}USART3_CK{slash}PD10_P_P-Pad57)") (class "Default")
      (node (ref "U2") (pin "57") (pinfunction "FSMC_D15/USART3_CK/PD10_P_P_57") (pintype "bidirectional"))
    )
    (net (code "58") (name "unconnected-(U2-FSMC_NBL0{slash}DCMI_D2{slash}PE0-Pad97)") (class "Default")
      (node (ref "U2") (pin "97") (pinfunction "FSMC_NBL0/DCMI_D2/PE0_97") (pintype "bidirectional"))
    )
    (net (code "59") (name "unconnected-(U2-FSMC_NBL1{slash}DCMI_D3{slash}PE1-Pad98)") (class "Default")
      (node (ref "U2") (pin "98") (pinfunction "FSMC_NBL1/DCMI_D3/PE1_98") (pintype "bidirectional"))
    )
    (net (code "60") (name "unconnected-(U2-FSMC_NE1{slash}FSMC_NCE2{slash}PD7-Pad88)") (class "Default")
      (node (ref "U2") (pin "88") (pinfunction "FSMC_NE1/FSMC_NCE2/PD7_88") (pintype "bidirectional"))
    )
    (net (code "61") (name "unconnected-(U2-FSMC_NOE{slash}USART2_RTS{slash}PD4-Pad85)") (class "Default")
      (node (ref "U2") (pin "85") (pinfunction "FSMC_NOE/USART2_RTS/PD4_85") (pintype "bidirectional"))
    )
    (net (code "62") (name "unconnected-(U2-FSMC_NWAIT{slash}USART2_RX{slash}PD6-Pad87)") (class "Default")
      (node (ref "U2") (pin "87") (pinfunction "FSMC_NWAIT/USART2_RX/PD6_87") (pintype "bidirectional"))
    )
    (net (code "63") (name "unconnected-(U2-FSMC_NWE{slash}USART2_TX{slash}PD5-Pad86)") (class "Default")
      (node (ref "U2") (pin "86") (pinfunction "FSMC_NWE/USART2_TX/PD5_86") (pintype "bidirectional"))
    )
    (net (code "64") (name "unconnected-(U2-I2S2_MCK{slash}SDIO_D6{slash}USART6_TX{slash}DCMI_D0{slash}PC6-Pad63)") (class "Default")
      (node (ref "U2") (pin "63") (pinfunction "I2S2_MCK/SDIO_D6/USART6_TX/DCMI_D0/PC6_63") (pintype "bidirectional"))
    )
    (net (code "65") (name "unconnected-(U2-I2S3_MCK{slash}SDIO_D7{slash}USART6_RX{slash}DCMI_D1{slash}PC7-Pad64)") (class "Default")
      (node (ref "U2") (pin "64") (pinfunction "I2S3_MCK/SDIO_D7/USART6_RX/DCMI_D1/PC7_64") (pintype "bidirectional"))
    )
    (net (code "66") (name "unconnected-(U2-I2S_CKIN{slash}MCO2{slash}SDIO_D1{slash}I2C3_SDA{slash}DCMI_D3{slash}PC9-Pad66)") (class "Default")
      (node (ref "U2") (pin "66") (pinfunction "I2S_CKIN/MCO2/SDIO_D1/I2C3_SDA/DCMI_D3/PC9_66") (pintype "bidirectional"))
    )
    (net (code "67") (name "unconnected-(U2-PA0-WKUP{slash}USART4_TX{slash}ADC123_IN0-Pad15)") (class "Default")
      (node (ref "U2") (pin "15") (pinfunction "PA0-WKUP/USART4_TX/ADC123_IN0_15") (pintype "bidirectional"))
    )
    (net (code "68") (name "unconnected-(U2-PA0-WKUP{slash}USART4_TX{slash}ADC123_IN0-Pad23)") (class "Default")
      (node (ref "U2") (pin "23") (pinfunction "PA0-WKUP/USART4_TX/ADC123_IN0_23") (pintype "bidirectional"))
    )
    (net (code "69") (name "unconnected-(U2-PA2{slash}USART2_TX{slash}ADC123_IN2{slash}ETH_MDIO-Pad25)") (class "Default")
      (node (ref "U2") (pin "25") (pinfunction "PA2/USART2_TX/ADC123_IN2/ETH_MDIO_25") (pintype "bidirectional"))
    )
    (net (code "70") (name "unconnected-(U2-PA3{slash}USART2_RX{slash}OTG_HS_ULPI_D0{slash}ADC123_IN3-Pad26)") (class "Default")
      (node (ref "U2") (pin "26") (pinfunction "PA3/USART2_RX/OTG_HS_ULPI_D0/ADC123_IN3_26") (pintype "bidirectional"))
    )
    (net (code "71") (name "unconnected-(U2-PA4{slash}DCMI_HSYNC{slash}OTG_HS_SOF{slash}I2S3_WS{slash}ADC12_IN4{slash}DAC1_OUT-Pad29)") (class "Default")
      (node (ref "U2") (pin "29") (pinfunction "PA4/DCMI_HSYNC/OTG_HS_SOF/I2S3_WS/ADC12_IN4/DAC1_OUT_29") (pintype "bidirectional"))
    )
    (net (code "72") (name "unconnected-(U2-PA8{slash}MCO1{slash}I2C3_SCL{slash}OTG_FS_SOF-Pad67)") (class "Default")
      (node (ref "U2") (pin "67") (pinfunction "PA8/MCO1/I2C3_SCL/OTG_FS_SOF_67") (pintype "bidirectional"))
    )
    (net (code "73") (name "unconnected-(U2-PA11{slash}CAN1_RX{slash}OTG_FS_DM-Pad70)") (class "Default")
      (node (ref "U2") (pin "70") (pinfunction "PA11/CAN1_RX/OTG_FS_DM_70") (pintype "bidirectional"))
    )
    (net (code "74") (name "unconnected-(U2-PA12{slash}CAN1_TX{slash}OTG_FS_DP-Pad71)") (class "Default")
      (node (ref "U2") (pin "71") (pinfunction "PA12/CAN1_TX/OTG_FS_DP_71") (pintype "bidirectional"))
    )
    (net (code "75") (name "unconnected-(U2-PA15{slash}JTDI{slash}I2S3_WS-Pad77)") (class "Default")
      (node (ref "U2") (pin "77") (pinfunction "PA15/JTDI/I2S3_WS_77") (pintype "bidirectional"))
    )
    (net (code "76") (name "unconnected-(U2-PB0{slash}OTG_HS_ULPI_D1{slash}ADC12_IN8-Pad35)") (class "Default")
      (node (ref "U2") (pin "35") (pinfunction "PB0/OTG_HS_ULPI_D1/ADC12_IN8_35") (pintype "bidirectional"))
    )
    (net (code "77") (name "unconnected-(U2-PB2{slash}BOOT1-Pad37)") (class "Default")
      (node (ref "U2") (pin "37") (pinfunction "PB2/BOOT1_37") (pintype "bidirectional"))
    )
    (net (code "78") (name "unconnected-(U2-PB3{slash}JTDO{slash}SPI3_SCK{slash}I2S3_CK{slash}SPI1_SCK-Pad89)") (class "Default")
      (node (ref "U2") (pin "89") (pinfunction "PB3/JTDO/SPI3_SCK/I2S3_CK/SPI1_SCK_89") (pintype "bidirectional"))
    )
    (net (code "79") (name "unconnected-(U2-PB4{slash}JNTRST{slash}SPI3_MISO{slash}SPI1_MISO{slash}I2S3ext_SD-Pad90)") (class "Default")
      (node (ref "U2") (pin "90") (pinfunction "PB4/JNTRST/SPI3_MISO/SPI1_MISO/I2S3ext_SD_90") (pintype "bidirectional"))
    )
    (net (code "80") (name "unconnected-(U2-PB5{slash}CAN2_RX{slash}OTG_HS_ULPI_D7{slash}DCMI_D10{slash}I2S3_SD-Pad91)") (class "Default")
      (node (ref "U2") (pin "91") (pinfunction "PB5/CAN2_RX/OTG_HS_ULPI_D7/DCMI_D10/I2S3_SD_91") (pintype "bidirectional"))
    )
    (net (code "81") (name "unconnected-(U2-PB6{slash}I2C1_SCL{slash}CAN2_TX{slash}OTG_FS_INTN{slash}DCMI_D5{slash}USART1_TX_2_2-Pad92)") (class "Default")
      (node (ref "U2") (pin "92") (pinfunction "PB6/I2C1_SCL/CAN2_TX/OTG_FS_INTN/DCMI_D5/USART1_TX_2_2_92") (pintype "bidirectional"))
    )
    (net (code "82") (name "unconnected-(U2-PB7{slash}I2C1_SDA{slash}FSMC_NL{slash}DCMI_VSYNC{slash}USART1_RX-Pad93)") (class "Default")
      (node (ref "U2") (pin "93") (pinfunction "PB7/I2C1_SDA/FSMC_NL/DCMI_VSYNC/USART1_RX_93") (pintype "bidirectional"))
    )
    (net (code "83") (name "unconnected-(U2-PB12{slash}I2S2_WS{slash}I2S2_SMBA{slash}CAN2_RX{slash}ETH_TXD0-Pad51)") (class "Default")
      (node (ref "U2") (pin "51") (pinfunction "PB12/I2S2_WS/I2S2_SMBA/CAN2_RX/ETH_TXD0_51") (pintype "bidirectional"))
    )
    (net (code "84") (name "unconnected-(U2-PB13{slash}SPI2_SCK{slash}I2S2_CK{slash}CAN2_TX{slash}ETH_TXD1-Pad52)") (class "Default")
      (node (ref "U2") (pin "52") (pinfunction "PB13/SPI2_SCK/I2S2_CK/CAN2_TX/ETH_TXD1_52") (pintype "bidirectional"))
    )
    (net (code "85") (name "unconnected-(U2-PB14{slash}SPI2_MISO{slash}OTG_HS_DMUSART3_53RTS{slash}I2S2ext_SD-Pad53)") (class "Default")
      (node (ref "U2") (pin "53") (pinfunction "PB14/SPI2_MISO/OTG_HS_DMUSART3_53RTS/I2S2ext_SD_53") (pintype "bidirectional"))
    )
    (net (code "86") (name "unconnected-(U2-PB15{slash}SPI2_MOSI{slash}I2S2_SD{slash}OTG_HS_DP-Pad54)") (class "Default")
      (node (ref "U2") (pin "54") (pinfunction "PB15/SPI2_MOSI/I2S2_SD/OTG_HS_DP_54") (pintype "bidirectional"))
    )
    (net (code "87") (name "unconnected-(U2-SDIO_D0{slash}DCMI_D2{slash}PC8-Pad65)") (class "Default")
      (node (ref "U2") (pin "65") (pinfunction "SDIO_D0/DCMI_D2/PC8_65") (pintype "bidirectional"))
    )
    (net (code "88") (name "unconnected-(U2-SPI2_MISO{slash}OTG_HS_ULPI_DIR{slash}I2S2ext_SD{slash}ADC123_IN12{slash}PC2-Pad17)") (class "Default")
      (node (ref "U2") (pin "17") (pinfunction "SPI2_MISO/OTG_HS_ULPI_DIR/I2S2ext_SD/ADC123_IN12/PC2_17") (pintype "bidirectional"))
    )
    (net (code "89") (name "unconnected-(U2-SPI2_MOSI{slash}I2S2_SD{slash}OTG_HS_ULPI_NXT{slash}ADC123_IN13{slash}PC3-Pad18)") (class "Default")
      (node (ref "U2") (pin "18") (pinfunction "SPI2_MOSI/I2S2_SD/OTG_HS_ULPI_NXT/ADC123_IN13/PC3_18") (pintype "bidirectional"))
    )
    (net (code "90") (name "unconnected-(U2-SPI3_SCK{slash}I2S3_CK{slash}UART4_TX{slash}SDIO_D2{slash}USART3_TX{slash}PC10-Pad78)") (class "Default")
      (node (ref "U2") (pin "78") (pinfunction "SPI3_SCK/I2S3_CK/UART4_TX/SDIO_D2/USART3_TX/PC10_78") (pintype "bidirectional"))
    )
    (net (code "91") (name "unconnected-(U2-TAMPER-RTC_AF1{slash}PC13-Pad7)") (class "Default")
      (node (ref "U2") (pin "7") (pinfunction "TAMPER-RTC_AF1/PC13_7") (pintype "bidirectional"))
    )
    (net (code "92") (name "unconnected-(U2-TRACECLK{slash}FSMC_A23{slash}PE2-Pad1)") (class "Default")
      (node (ref "U2") (pin "1") (pinfunction "TRACECLK/FSMC_A23/PE2_1") (pintype "bidirectional"))
    )
    (net (code "93") (name "unconnected-(U2-TRACED0{slash}FSMC_A19{slash}PE3-Pad2)") (class "Default")
      (node (ref "U2") (pin "2") (pinfunction "TRACED0/FSMC_A19/PE3_2") (pintype "bidirectional"))
    )
    (net (code "94") (name "unconnected-(U2-TRACED1{slash}FSMC_A20{slash}DCMI_D4{slash}PE4-Pad3)") (class "Default")
      (node (ref "U2") (pin "3") (pinfunction "TRACED1/FSMC_A20/DCMI_D4/PE4_3") (pintype "bidirectional"))
    )
    (net (code "95") (name "unconnected-(U2-TRACED2{slash}FSMC_A21{slash}DCMI_D6{slash}PE5-Pad4)") (class "Default")
      (node (ref "U2") (pin "4") (pinfunction "TRACED2/FSMC_A21/DCMI_D6/PE5_4") (pintype "bidirectional"))
    )
    (net (code "96") (name "unconnected-(U2-TRACED3{slash}FSMC_A22{slash}DCMI_D7{slash}PE6-Pad5)") (class "Default")
      (node (ref "U2") (pin "5") (pinfunction "TRACED3/FSMC_A22/DCMI_D7/PE6_5") (pintype "bidirectional"))
    )
    (net (code "97") (name "unconnected-(U2-UART4_RX{slash}SPI3_MISO{slash}SDIO_D3{slash}DCMI_D4{slash}USART3_RX{slash}I2S3ext_SD{slash}PC11-Pad79)") (class "Default")
      (node (ref "U2") (pin "79") (pinfunction "UART4_RX/SPI3_MISO/SDIO_D3/DCMI_D4/USART3_RX/I2S3ext_SD/PC11_79") (pintype "bidirectional"))
    )
    (net (code "98") (name "unconnected-(U2-UART5_RXSDIO_CMD{slash}DCMI_D11{slash}PD2-Pad83)") (class "Default")
      (node (ref "U2") (pin "83") (pinfunction "UART5_RXSDIO_CMD/DCMI_D11/PD2_83") (pintype "bidirectional"))
    )
    (net (code "99") (name "unconnected-(U2-UART5_TX{slash}SDIO_CK{slash}DCMI_D9{slash}SPI3_MOSI{slash}I2S3_SD{slash}USART3_CK{slash}PC12-Pad80)") (class "Default")
      (node (ref "U2") (pin "80") (pinfunction "UART5_TX/SDIO_CK/DCMI_D9/SPI3_MOSI/I2S3_SD/USART3_CK/PC12_80") (pintype "bidirectional"))
    )
    (net (code "100") (name "unconnected-(U2-VREF+-Pad21)") (class "Default")
      (node (ref "U2") (pin "21") (pinfunction "VREF+_21") (pintype "power_in"))
    )
    (net (code "101") (name "unconnected-(U3-ADC-Pad2)") (class "Default")
      (node (ref "U3") (pin "2") (pinfunction "ADC_2") (pintype "passive"))
    )
    (net (code "102") (name "unconnected-(U3-EN-Pad3)") (class "Default")
      (node (ref "U3") (pin "3") (pinfunction "EN_3") (pintype "passive"))
    )
    (net (code "103") (name "unconnected-(U3-IO0-Pad12)") (class "Default")
      (node (ref "U3") (pin "12") (pinfunction "IO0_12") (pintype "passive"))
    )
    (net (code "104") (name "unconnected-(U3-IO2-Pad11)") (class "Default")
      (node (ref "U3") (pin "11") (pinfunction "IO2_11") (pintype "passive"))
    )
    (net (code "105") (name "unconnected-(U3-IO4-Pad13)") (class "Default")
      (node (ref "U3") (pin "13") (pinfunction "IO4_13") (pintype "passive"))
    )
    (net (code "106") (name "unconnected-(U3-IO5-Pad14)") (class "Default")
      (node (ref "U3") (pin "14") (pinfunction "IO5_14") (pintype "passive"))
    )
    (net (code "107") (name "unconnected-(U3-IO12-Pad6)") (class "Default")
      (node (ref "U3") (pin "6") (pinfunction "IO12_6") (pintype "passive"))
    )
    (net (code "108") (name "unconnected-(U3-IO13-Pad7)") (class "Default")
      (node (ref "U3") (pin "7") (pinfunction "IO13_7") (pintype "passive"))
    )
    (net (code "109") (name "unconnected-(U3-IO14-Pad5)") (class "Default")
      (node (ref "U3") (pin "5") (pinfunction "IO14_5") (pintype "passive"))
    )
    (net (code "110") (name "unconnected-(U3-IO15-Pad10)") (class "Default")
      (node (ref "U3") (pin "10") (pinfunction "IO15_10") (pintype "passive"))
    )
    (net (code "111") (name "unconnected-(U3-IO16-Pad4)") (class "Default")
      (node (ref "U3") (pin "4") (pinfunction "IO16_4") (pintype "passive"))
    )
    (net (code "112") (name "unconnected-(U4-D+-Pad3)") (class "Default")
      (node (ref "U4") (pin "3") (pinfunction "D+_3") (pintype "passive"))
    )
    (net (code "113") (name "unconnected-(U4-D--Pad2)") (class "Default")
      (node (ref "U4") (pin "2") (pinfunction "D-_2") (pintype "passive"))
    )
    (net (code "114") (name "unconnected-(U4-NC-Pad4)") (class "Default")
      (node (ref "U4") (pin "4") (pinfunction "NC_4") (pintype "passive"))
    )
  )
)
